# opto_io.net
KiCad netlist of a schematic drawn in Altium Designer
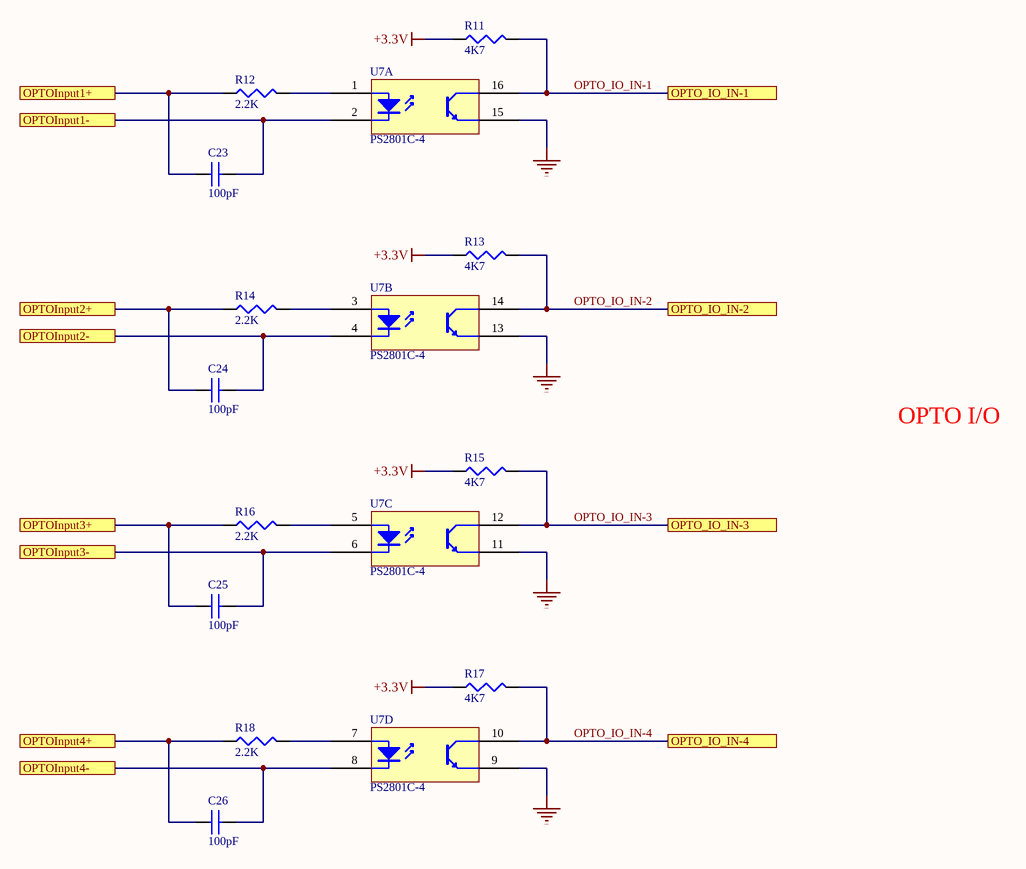
[diagram p0: opto_io.schdoc]

(export (version "E")
  (design (tool "Eeschema 10.0.6"))
  (components
    (comp (ref "C23")
      (value "100pF")
      (footprint "0805 SMD Ceramic Capacitor")
      (fields
        (field (name "VOLTAGE") "250V")
        (field (name "MANUFACTURER") "MURATA Electronics")
        (field (name "TOLERANCE") "±5%")
      )
      (libsource (lib "Capacitors") (part "C0805C101"))
    )
    (comp (ref "C24")
      (value "100pF")
      (footprint "0805 SMD Ceramic Capacitor")
      (fields
        (field (name "VOLTAGE") "250V")
        (field (name "MANUFACTURER") "MURATA Electronics")
        (field (name "TOLERANCE") "±5%")
      )
      (libsource (lib "Capacitors") (part "C0805C101"))
    )
    (comp (ref "C25")
      (value "100pF")
      (footprint "0805 SMD Ceramic Capacitor")
      (fields
        (field (name "VOLTAGE") "250V")
        (field (name "MANUFACTURER") "MURATA Electronics")
        (field (name "TOLERANCE") "±5%")
      )
      (libsource (lib "Capacitors") (part "C0805C101"))
    )
    (comp (ref "C26")
      (value "100pF")
      (footprint "0805 SMD Ceramic Capacitor")
      (fields
        (field (name "VOLTAGE") "250V")
        (field (name "MANUFACTURER") "MURATA Electronics")
        (field (name "TOLERANCE") "±5%")
      )
      (libsource (lib "Capacitors") (part "C0805C101"))
    )
    (comp (ref "R11")
      (value "4K7")
      (footprint "0805 Resistor")
      (fields
        (field (name "TOLERANCE") "±0.1%")
        (field (name "MANUFACTURER") "WELWYN")
        (field (name "Comment") "0805_4K7%1")
      )
      (libsource (lib "Resistors") (part "0805_4K7%1"))
    )
    (comp (ref "R12")
      (value "2.2K")
      (footprint "0805 Resistor")
      (fields
        (field (name "TOLERANCE") "±1%")
        (field (name "MANUFACTURER") "MULTICOMP")
        (field (name "Comment") "0805_1K")
      )
      (libsource (lib "Resistors") (part "0805_1K"))
    )
    (comp (ref "R13")
      (value "4K7")
      (footprint "0805 Resistor")
      (fields
        (field (name "TOLERANCE") "±0.1%")
        (field (name "MANUFACTURER") "WELWYN")
        (field (name "Comment") "0805_4K7%1")
      )
      (libsource (lib "Resistors") (part "0805_4K7%1"))
    )
    (comp (ref "R14")
      (value "2.2K")
      (footprint "0805 Resistor")
      (fields
        (field (name "TOLERANCE") "±1%")
        (field (name "MANUFACTURER") "MULTICOMP")
        (field (name "Comment") "0805_1K")
      )
      (libsource (lib "Resistors") (part "0805_1K"))
    )
    (comp (ref "R15")
      (value "4K7")
      (footprint "0805 Resistor")
      (fields
        (field (name "TOLERANCE") "±0.1%")
        (field (name "MANUFACTURER") "WELWYN")
        (field (name "Comment") "0805_4K7%1")
      )
      (libsource (lib "Resistors") (part "0805_4K7%1"))
    )
    (comp (ref "R16")
      (value "2.2K")
      (footprint "0805 Resistor")
      (fields
        (field (name "TOLERANCE") "±1%")
        (field (name "MANUFACTURER") "MULTICOMP")
        (field (name "Comment") "0805_1K")
      )
      (libsource (lib "Resistors") (part "0805_1K"))
    )
    (comp (ref "R17")
      (value "4K7")
      (footprint "0805 Resistor")
      (fields
        (field (name "TOLERANCE") "±0.1%")
        (field (name "MANUFACTURER") "WELWYN")
        (field (name "Comment") "0805_4K7%1")
      )
      (libsource (lib "Resistors") (part "0805_4K7%1"))
    )
    (comp (ref "R18")
      (value "2.2K")
      (footprint "0805 Resistor")
      (fields
        (field (name "TOLERANCE") "±1%")
        (field (name "MANUFACTURER") "MULTICOMP")
        (field (name "Comment") "0805_1K")
      )
      (libsource (lib "Resistors") (part "0805_1K"))
    )
    (comp (ref "U7")
      (value "PS2801C-4")
      (footprint "SO16")
      (fields (field (name "MANUFACTURER") "NEC") (field (name "Comment") "PS2801C-4_Discrete"))
      (libsource (lib "PS2801C-4") (part "PS2801C-4_Discrete"))
    )
  )
  (nets
    (net (code "1") (name "+3.3V") (class "Default")
      (node (ref "R11") (pin "1") (pinfunction "1_1") (pintype "passive"))
      (node (ref "R13") (pin "1") (pinfunction "1_1") (pintype "passive"))
      (node (ref "R15") (pin "1") (pinfunction "1_1") (pintype "passive"))
      (node (ref "R17") (pin "1") (pinfunction "1_1") (pintype "passive"))
    )
    (net (code "2") (name "/OPTOInput1+") (class "Default")
      (node (ref "C23") (pin "1") (pinfunction "1_1") (pintype "passive"))
      (node (ref "R12") (pin "1") (pinfunction "1_1") (pintype "passive"))
    )
    (net (code "3") (name "/OPTOInput1-") (class "Default")
      (node (ref "C23") (pin "2") (pinfunction "2_2") (pintype "passive"))
      (node (ref "U7") (pin "2") (pintype "passive"))
    )
    (net (code "4") (name "/OPTOInput2+") (class "Default")
      (node (ref "C24") (pin "1") (pinfunction "1_1") (pintype "passive"))
      (node (ref "R14") (pin "1") (pinfunction "1_1") (pintype "passive"))
    )
    (net (code "5") (name "/OPTOInput2-") (class "Default")
      (node (ref "C24") (pin "2") (pinfunction "2_2") (pintype "passive"))
      (node (ref "U7") (pin "4") (pintype "passive"))
    )
    (net (code "6") (name "/OPTOInput3+") (class "Default")
      (node (ref "C25") (pin "1") (pinfunction "1_1") (pintype "passive"))
      (node (ref "R16") (pin "1") (pinfunction "1_1") (pintype "passive"))
    )
    (net (code "7") (name "/OPTOInput3-") (class "Default")
      (node (ref "C25") (pin "2") (pinfunction "2_2") (pintype "passive"))
      (node (ref "U7") (pin "6") (pintype "passive"))
    )
    (net (code "8") (name "/OPTOInput4+") (class "Default")
      (node (ref "C26") (pin "1") (pinfunction "1_1") (pintype "passive"))
      (node (ref "R18") (pin "1") (pinfunction "1_1") (pintype "passive"))
    )
    (net (code "9") (name "/OPTOInput4-") (class "Default")
      (node (ref "C26") (pin "2") (pinfunction "2_2") (pintype "passive"))
      (node (ref "U7") (pin "8") (pintype "passive"))
    )
    (net (code "10") (name "/OPTO_IO_IN-1") (class "Default")
      (node (ref "R11") (pin "2") (pinfunction "2_2") (pintype "passive"))
      (node (ref "U7") (pin "16") (pintype "passive"))
    )
    (net (code "11") (name "/OPTO_IO_IN-2") (class "Default")
      (node (ref "R13") (pin "2") (pinfunction "2_2") (pintype "passive"))
      (node (ref "U7") (pin "14") (pintype "passive"))
    )
    (net (code "12") (name "/OPTO_IO_IN-3") (class "Default")
      (node (ref "R15") (pin "2") (pinfunction "2_2") (pintype "passive"))
      (node (ref "U7") (pin "12") (pintype "passive"))
    )
    (net (code "13") (name "/OPTO_IO_IN-4") (class "Default")
      (node (ref "R17") (pin "2") (pinfunction "2_2") (pintype "passive"))
      (node (ref "U7") (pin "10") (pintype "passive"))
    )
    (net (code "14") (name "GND") (class "Default")
      (node (ref "U7") (pin "11") (pintype "passive"))
      (node (ref "U7") (pin "13") (pintype "passive"))
      (node (ref "U7") (pin "15") (pintype "passive"))
      (node (ref "U7") (pin "9") (pintype "passive"))
    )
    (net (code "15") (name "Net-(R12-Pad2)") (class "Default")
      (node (ref "R12") (pin "2") (pinfunction "2_2") (pintype "passive"))
      (node (ref "U7") (pin "1") (pintype "passive"))
    )
    (net (code "16") (name "Net-(R14-Pad2)") (class "Default")
      (node (ref "R14") (pin "2") (pinfunction "2_2") (pintype "passive"))
      (node (ref "U7") (pin "3") (pintype "passive"))
    )
    (net (code "17") (name "Net-(R16-Pad2)") (class "Default")
      (node (ref "R16") (pin "2") (pinfunction "2_2") (pintype "passive"))
      (node (ref "U7") (pin "5") (pintype "passive"))
    )
    (net (code "18") (name "Net-(R18-Pad2)") (class "Default")
      (node (ref "R18") (pin "2") (pinfunction "2_2") (pintype "passive"))
      (node (ref "U7") (pin "7") (pintype "passive"))
    )
  )
)
